# Schematic_relay.net
KiCad netlist of a schematic drawn in Altium Designer
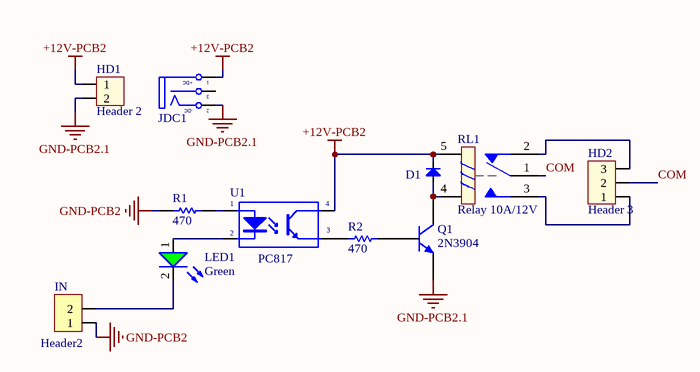
[diagram p0: Schematic_relay.SchDoc]

(export (version "E")
  (design (tool "Eeschema 10.0.6"))
  (components
    (comp (ref "D1")
      (value "Diode")
      (footprint "DIO-1A-SMALL")
      (description "Default Diode")
      (fields (field (name "PUBLISHER") "Altium Limited"))
      (libsource (lib "TechMT.VN_Lib_Project v2") (part "Diode"))
    )
    (comp (ref "HD1")
      (value "Header 2")
      (footprint "HED2")
      (description "Header 2 (Green)")
      (libsource (lib "syhaunguyen") (part "Hed2"))
    )
    (comp (ref "HD2")
      (value "Header 3")
      (footprint "HED3B")
      (description "Header 3 (Green)")
      (libsource (lib "syhaunguyen") (part "Hed3"))
    )
    (comp (ref "IN")
      (value "Header2")
      (footprint "HDR2")
      (description "Header IDC, 2 x 1 Pin Vertical 2.54mm Pitch (Non-Boxed, Male)")
      (fields
        (field (name "MANUFACTURER") "Würth Elektronik eiSos GmbH")
        (field (name "PARTNO") "613002143121")
        (field (name "CREATED BY") "Karrer Zheng")
      )
      (libsource (lib "TechMT.VN_Lib_Project v2") (part "Header2"))
    )
    (comp (ref "JDC1")
      (value "Jack DC")
      (footprint "DC-IN")
      (description "Jack DC input")
      (libsource (lib "TechMT.VN_Lib_Project v1.0") (part "Jack DC"))
    )
    (comp (ref "LED1")
      (value "Green")
      (footprint "LED3G")
      (description "LED Green 3mm")
      (fields (field (name "Comment") "LED_G_3"))
      (libsource (lib "TechMT.VN_Lib_Project v1.0") (part "LED_GREEN_3MM"))
    )
    (comp (ref "Q1")
      (value "2N3904")
      (footprint "TO-92A")
      (description "NPN General Purpose Amplifier")
      (fields (field (name "PUBLISHER") "Altium Limited"))
      (libsource (lib "Miscellaneous Devices") (part "2N3904"))
    )
    (comp (ref "R1")
      (value "470")
      (footprint "RES 1/2W")
      (description "Resistor")
      (fields (field (name "Comment") "RESISTOR"))
      (libsource (lib "TechMT.VN_Lib_Project v1.0") (part "RESISTOR"))
    )
    (comp (ref "R2")
      (value "470")
      (footprint "RES 1/2W")
      (description "Resistor")
      (fields (field (name "Comment") "RESISTOR"))
      (libsource (lib "TechMT.VN_Lib_Project v1.0") (part "RESISTOR"))
    )
    (comp (ref "RL1")
      (value "Relay 10A/12V")
      (footprint "RELAY 5")
      (description "Relay SPDT,10A - 12VDC 5 Pin")
      (libsource (lib "TechMT.VN_Lib_Project v2") (part "Relay 5"))
    )
    (comp (ref "U1")
      (value "PC817")
      (footprint "DIP4")
      (description "Single Opto")
      (libsource (lib "TechMT.VN_Lib_Project v2") (part "PC817"))
    )
  )
  (nets
    (net (code "1") (name "+12V-PCB2") (class "Default")
      (node (ref "D1") (pin "2") (pinfunction "K_2") (pintype "passive"))
      (node (ref "HD1") (pin "1") (pinfunction "1_1") (pintype "passive"))
      (node (ref "JDC1") (pin "1") (pinfunction "T_1") (pintype "passive"))
      (node (ref "RL1") (pin "5") (pinfunction "5_5") (pintype "passive"))
      (node (ref "U1") (pin "4") (pinfunction "C_4") (pintype "passive"))
    )
    (net (code "2") (name "/COM") (class "Default")
      (node (ref "HD2") (pin "2") (pinfunction "2_2") (pintype "passive"))
      (node (ref "RL1") (pin "1") (pinfunction "1_1") (pintype "passive"))
    )
    (net (code "3") (name "GND-PCB2") (class "Default")
      (node (ref "IN") (pin "1") (pinfunction "1_1") (pintype "passive"))
      (node (ref "R1") (pin "1") (pinfunction "1_1") (pintype "passive"))
    )
    (net (code "4") (name "GND-PCB2.1") (class "Default")
      (node (ref "HD1") (pin "2") (pinfunction "2_2") (pintype "passive"))
      (node (ref "JDC1") (pin "2") (pinfunction "TN_2") (pintype "passive"))
      (node (ref "Q1") (pin "1") (pinfunction "E_1") (pintype "passive"))
    )
    (net (code "5") (name "Net-(D1-A)") (class "Default")
      (node (ref "D1") (pin "1") (pinfunction "A_1") (pintype "passive"))
      (node (ref "Q1") (pin "3") (pinfunction "C_3") (pintype "passive"))
      (node (ref "RL1") (pin "4") (pinfunction "4_4") (pintype "passive"))
    )
    (net (code "6") (name "Net-(HD2-Pad1)") (class "Default")
      (node (ref "HD2") (pin "1") (pinfunction "1_1") (pintype "passive"))
      (node (ref "RL1") (pin "3") (pinfunction "3_3") (pintype "passive"))
    )
    (net (code "7") (name "Net-(HD2-Pad3)") (class "Default")
      (node (ref "HD2") (pin "3") (pinfunction "3_3") (pintype "passive"))
      (node (ref "RL1") (pin "2") (pinfunction "2_2") (pintype "passive"))
    )
    (net (code "8") (name "Net-(LED1-A)") (class "Default")
      (node (ref "LED1") (pin "1") (pinfunction "A_1") (pintype "passive"))
      (node (ref "U1") (pin "2") (pinfunction "K_2") (pintype "passive"))
    )
    (net (code "9") (name "Net-(LED1-K)") (class "Default")
      (node (ref "IN") (pin "2") (pinfunction "2_2") (pintype "passive"))
      (node (ref "LED1") (pin "2") (pinfunction "K_2") (pintype "passive"))
    )
    (net (code "10") (name "Net-(Q1-B)") (class "Default")
      (node (ref "Q1") (pin "2") (pinfunction "B_2") (pintype "passive"))
      (node (ref "R2") (pin "2") (pinfunction "2_2") (pintype "passive"))
    )
    (net (code "11") (name "Net-(U1-A)") (class "Default")
      (node (ref "R1") (pin "2") (pinfunction "2_2") (pintype "passive"))
      (node (ref "U1") (pin "1") (pinfunction "A_1") (pintype "passive"))
    )
    (net (code "12") (name "Net-(U1-E)") (class "Default")
      (node (ref "R2") (pin "1") (pinfunction "1_1") (pintype "passive"))
      (node (ref "U1") (pin "3") (pinfunction "E_3") (pintype "passive"))
    )
    (net (code "13") (name "unconnected-(JDC1-S-Pad3)") (class "Default")
      (node (ref "JDC1") (pin "3") (pinfunction "S_3") (pintype "power_in"))
    )
  )
)
